# Bike_Alpha.net
KiCad netlist of a schematic drawn in EasyEDA
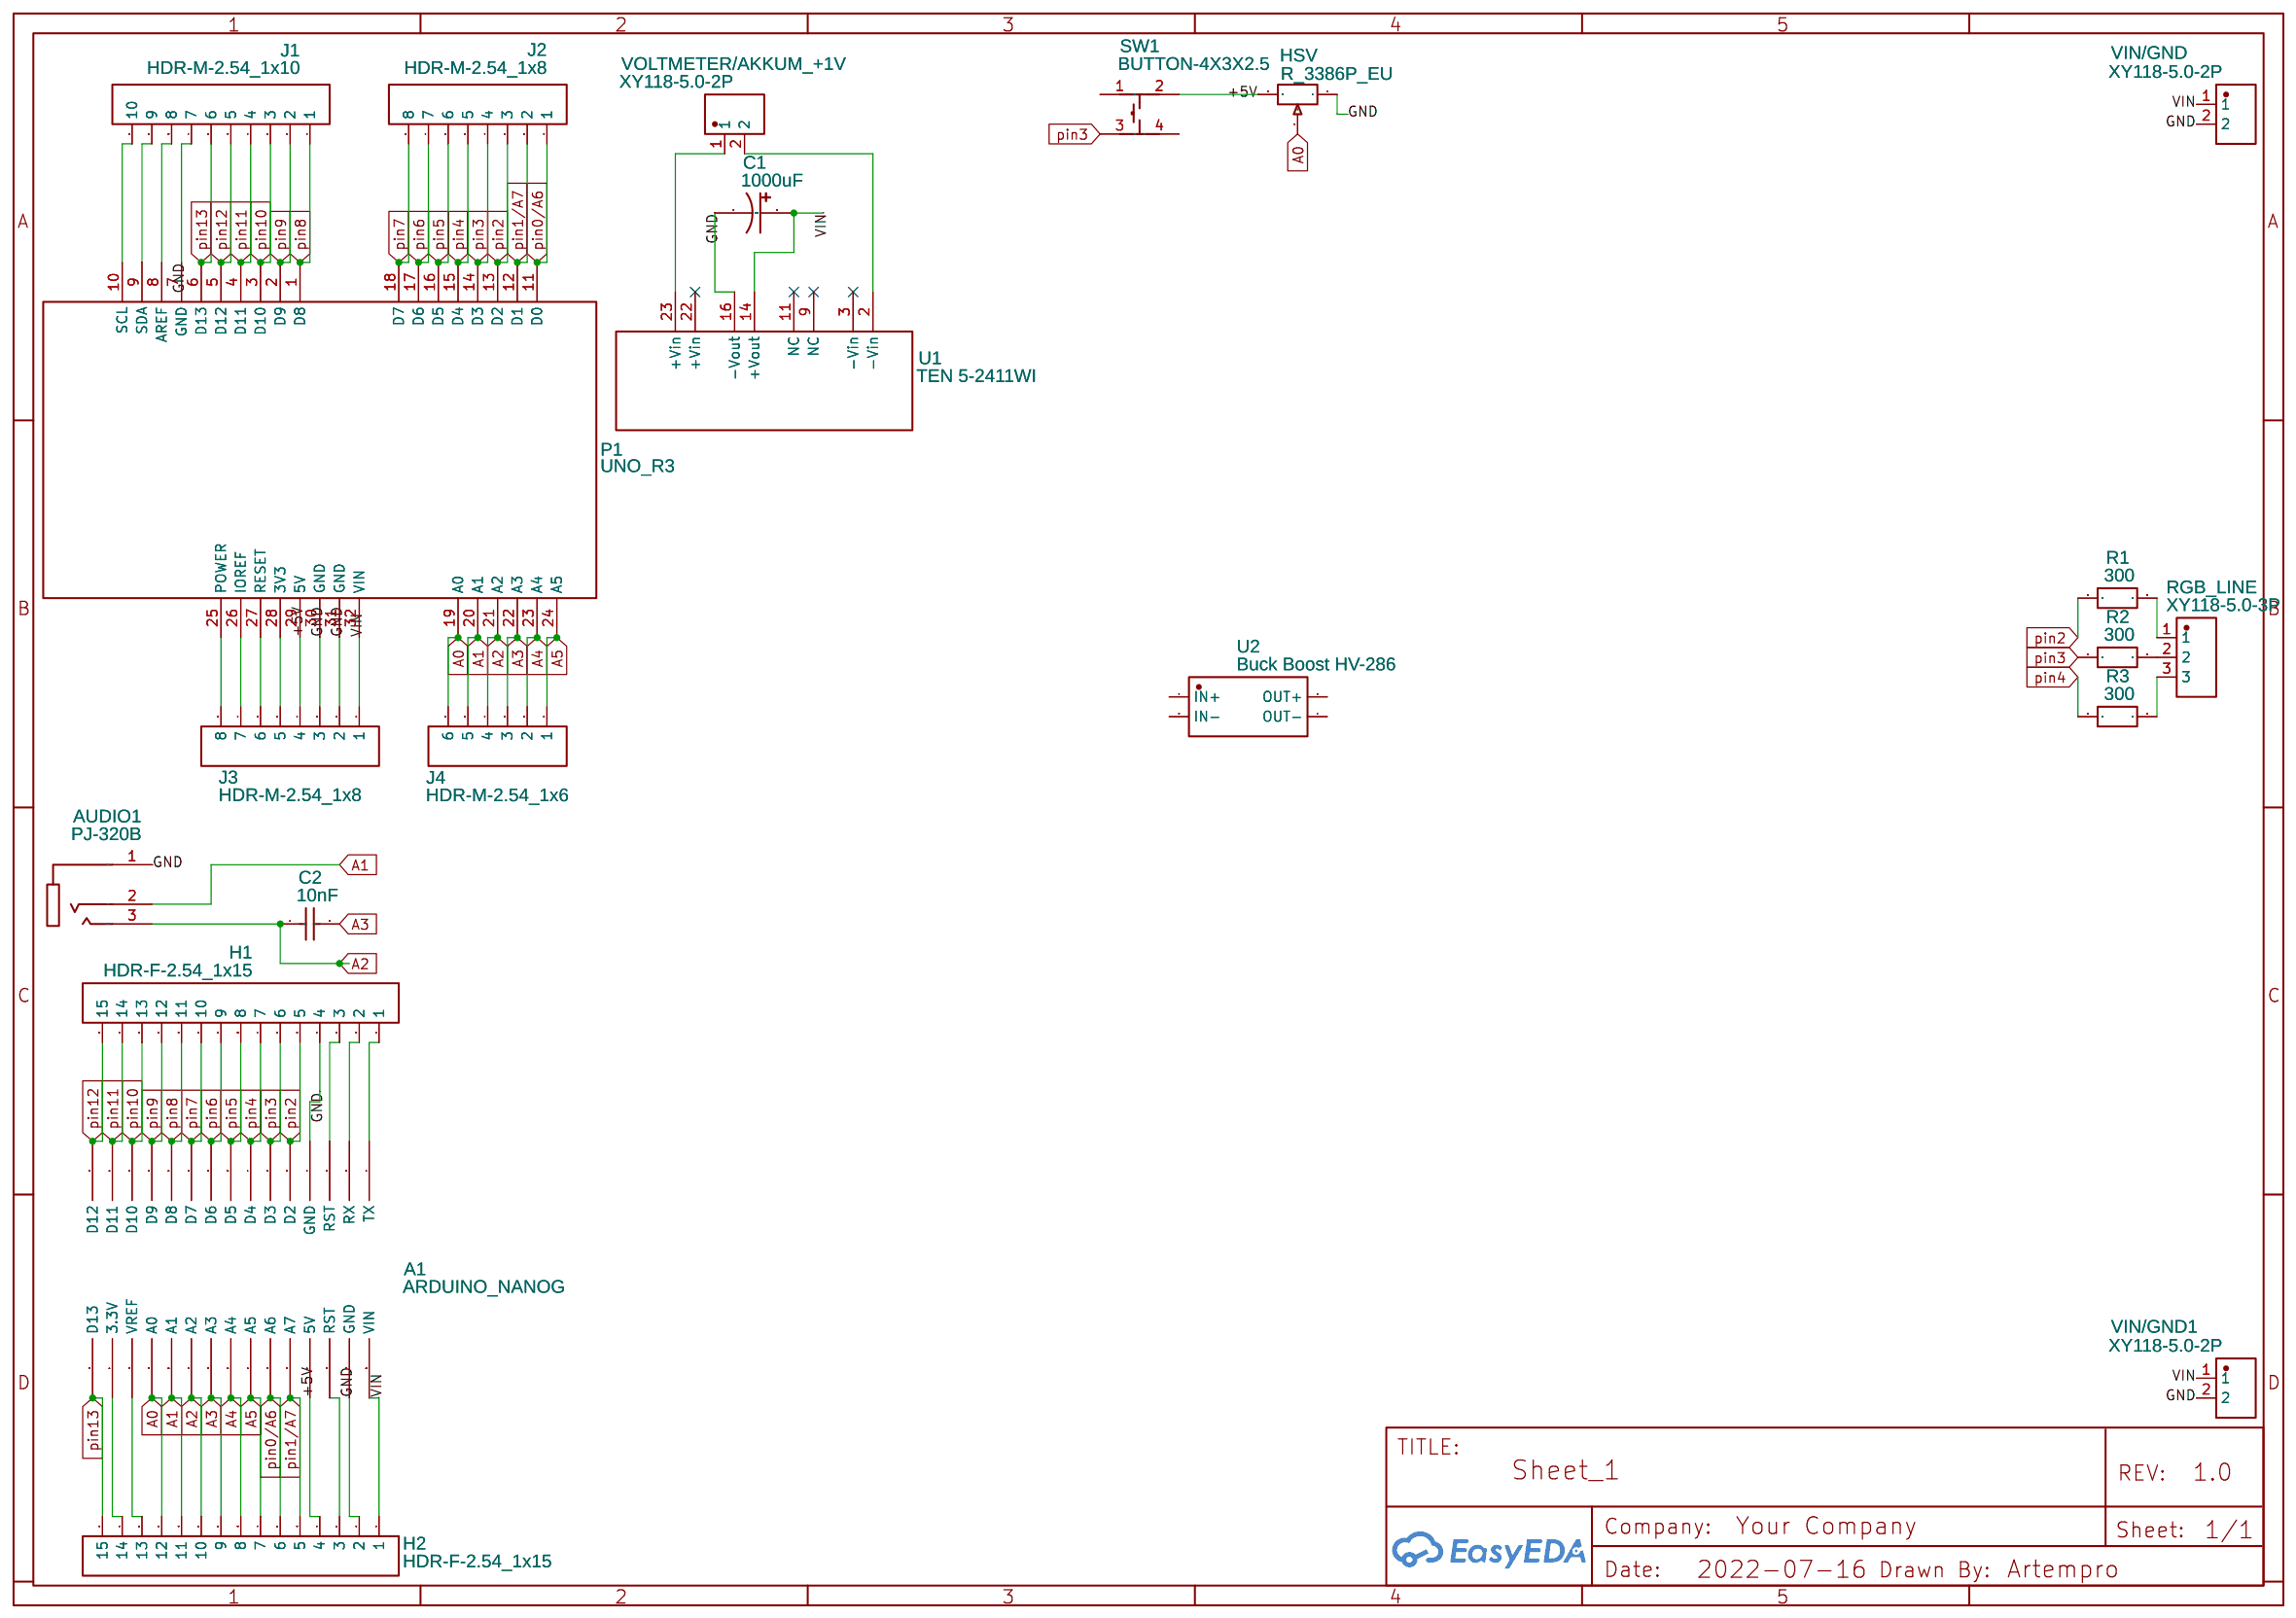
[diagram p0: Sheet_1]
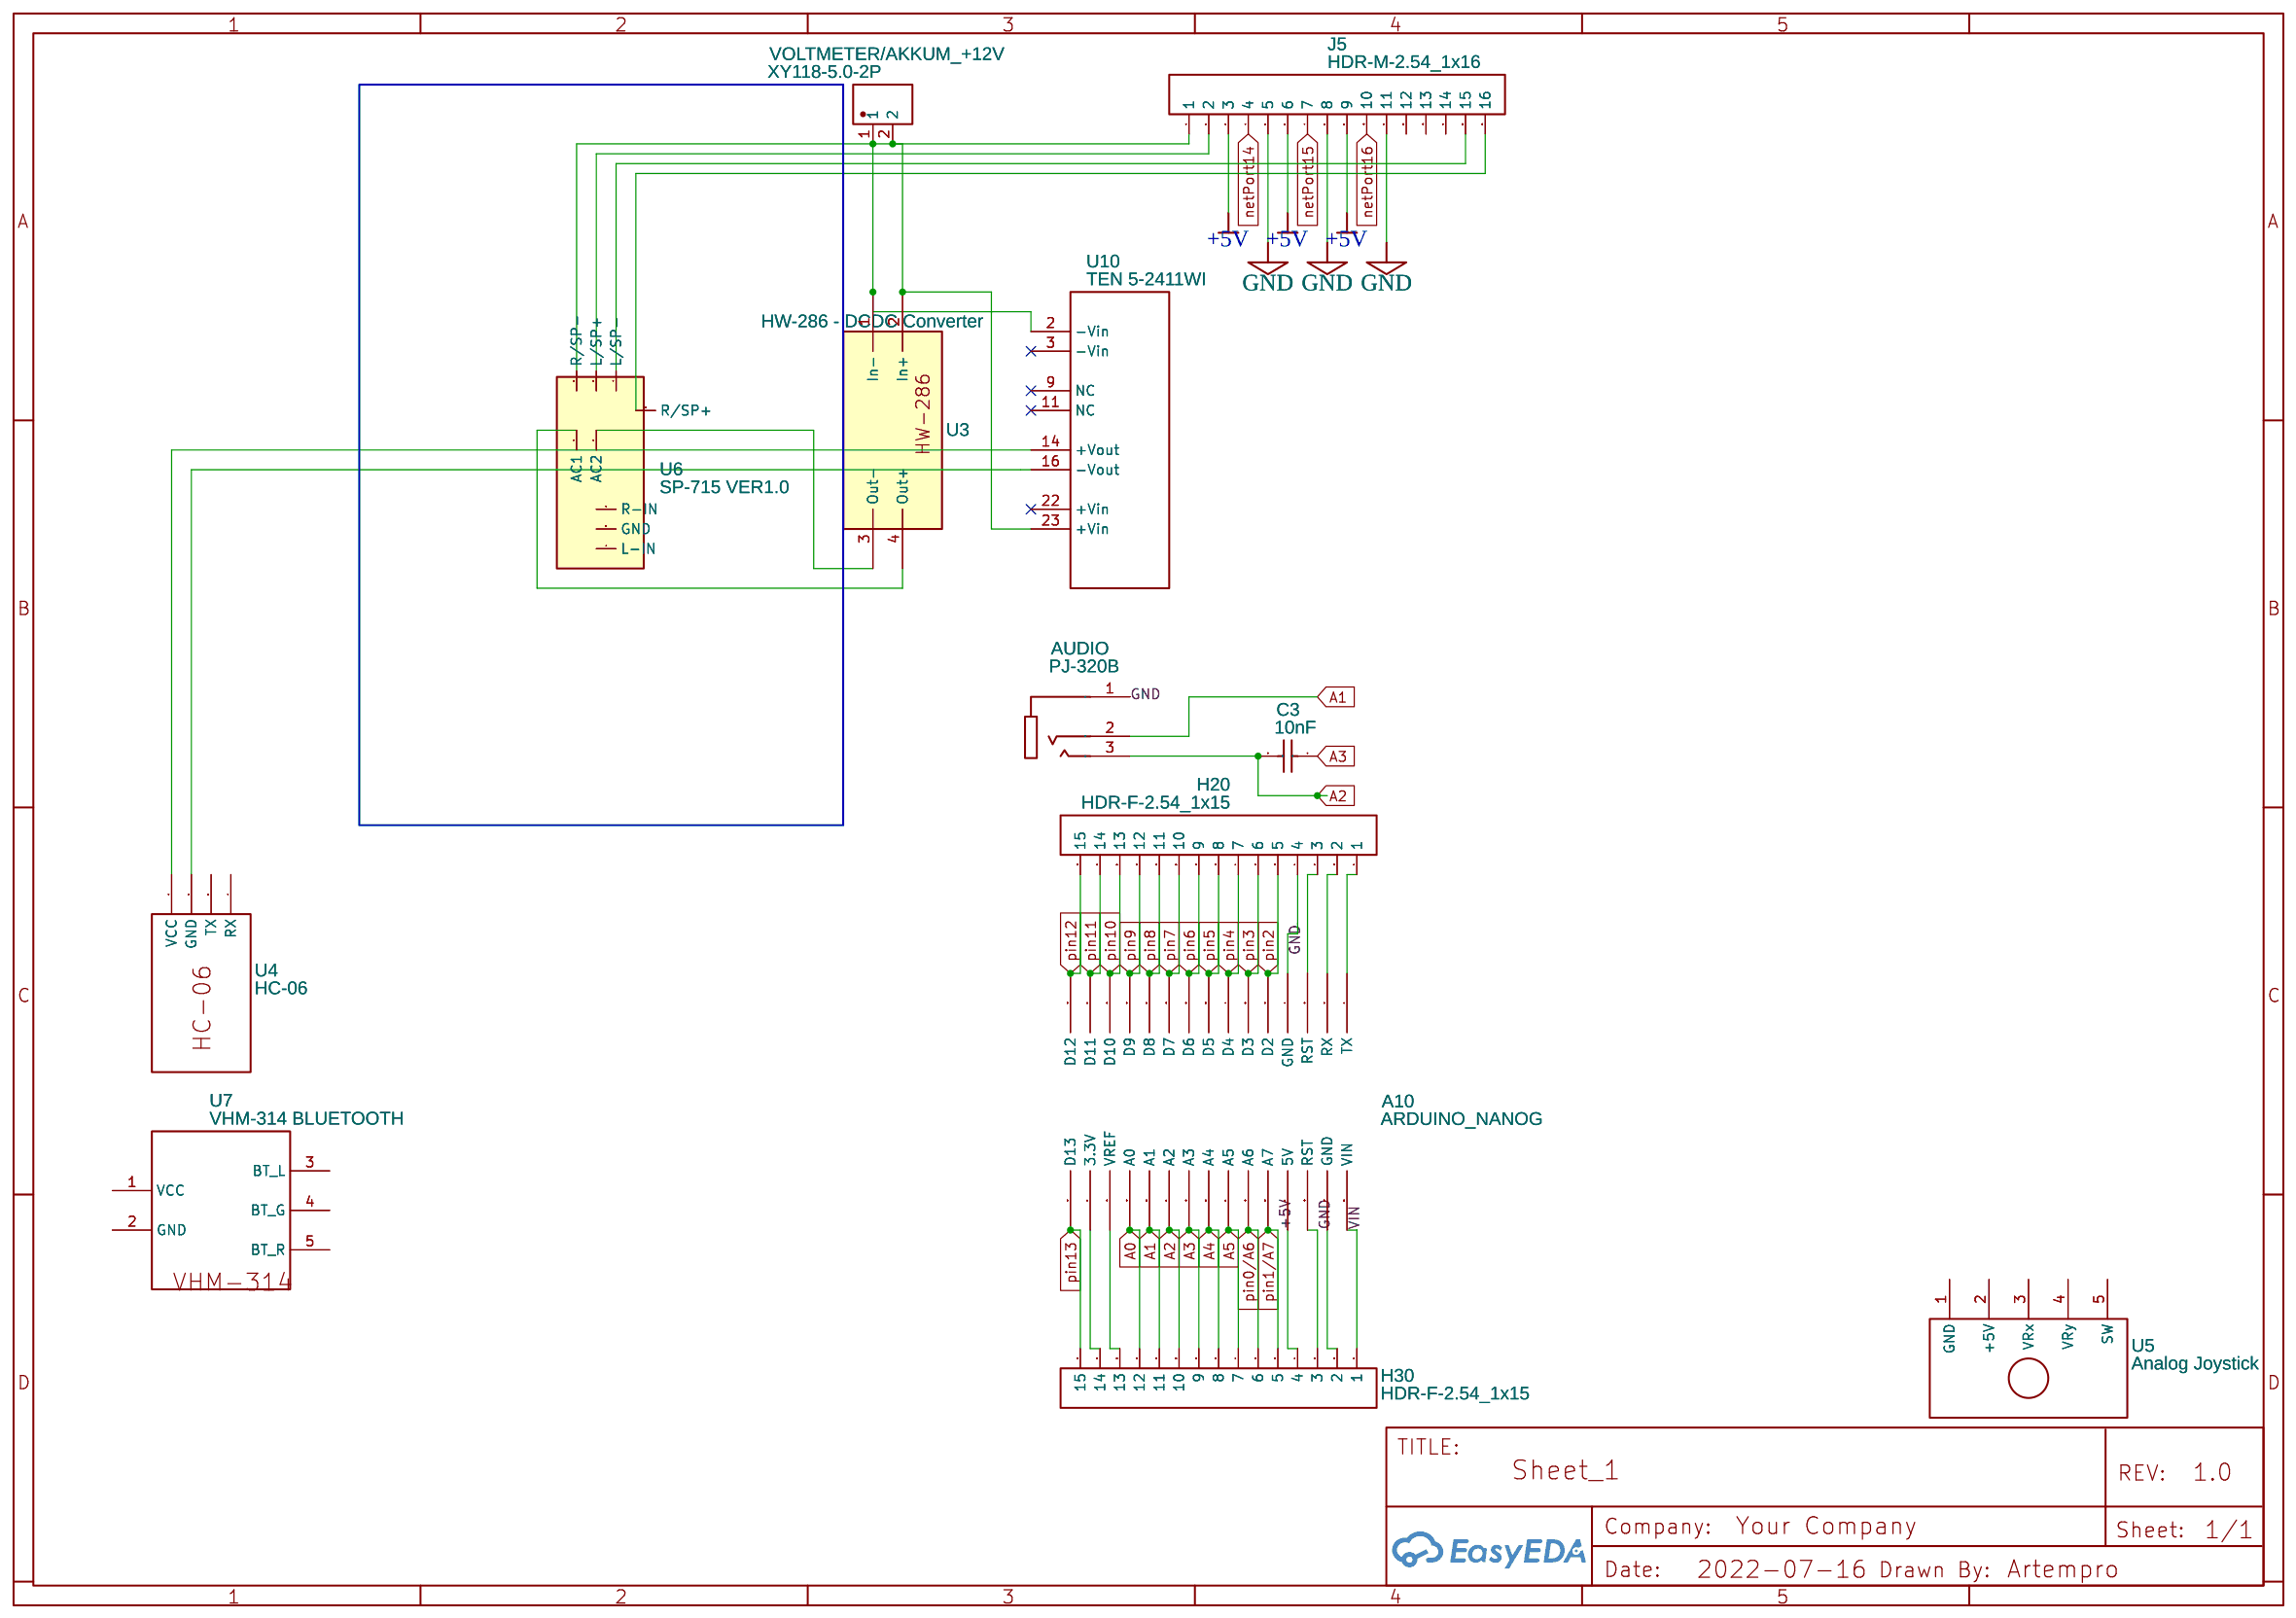
[diagram p1: Add multi media]

(export (version "E")
  (design (tool "Eeschema 10.0.6"))
  (components
    (comp (ref "A1")
      (value "ARDUINO_NANOG")
      (fields (field (name "BOM_Manufacturer Part") "Arduino Nano"))
      (libsource (lib "") (part "ARDUINO_NANOG"))
    )
    (comp (ref "AUDIO1")
      (value "PJ-320B")
      (fields (field (name "BOM_Supplier Part") "C18594"))
      (libsource (lib "") (part "PJ-320B"))
    )
    (comp (ref "C1")
      (value "1000uF")
      (fields
        (field (name "BOM_Manufacturer Part") "RGA102MOJBK-0811")
        (field (name "BOM_Supplier Part") "C311644")
      )
      (libsource (lib "") (part "RGA102MOJBK-0811"))
    )
    (comp (ref "C2")
      (value "10nF")
      (fields
        (field (name "BOM_Manufacturer Part") "DE2F3KY103MN3AM02F")
        (field (name "BOM_Supplier Part") "C85855")
      )
      (libsource (lib "") (part "DE2F3KY103MN3AM02F"))
    )
    (comp (ref "H1")
      (value "HDR-F-2.54_1x15")
      (fields (field (name "BOM_Supplier Part") "C124408"))
      (libsource (lib "") (part "HDR-F-2.54_1x15"))
    )
    (comp (ref "H2")
      (value "HDR-F-2.54_1x15")
      (fields (field (name "BOM_Supplier Part") "C124408"))
      (libsource (lib "") (part "HDR-F-2.54_1x15_1"))
    )
    (comp (ref "HSV") (value "R_3386P_EU") (libsource (lib "") (part "R_3386P_EU")))
    (comp (ref "J1")
      (value "HDR-M-2.54_1x10")
      (fields (field (name "BOM_Supplier Part") "C57369"))
      (libsource (lib "") (part "HDR-M-2.54_1x10"))
    )
    (comp (ref "J2")
      (value "HDR-M-2.54_1x8")
      (fields (field (name "BOM_Supplier Part") "C190820"))
      (libsource (lib "") (part "HDR-M-2.54_1x8"))
    )
    (comp (ref "J3")
      (value "HDR-M-2.54_1x8")
      (fields (field (name "BOM_Supplier Part") "C190820"))
      (libsource (lib "") (part "HDR-M-2.54_1x8_1"))
    )
    (comp (ref "J4")
      (value "HDR-M-2.54_1x6")
      (fields (field (name "BOM_Supplier Part") "C190819"))
      (libsource (lib "") (part "HDR-M-2.54_1x6"))
    )
    (comp (ref "P1") (value "UNO_R3") (libsource (lib "") (part "UNO_R3")))
    (comp (ref "R1")
      (value "300")
      (fields
        (field (name "BOM_Manufacturer Part") "RD 1/4W 300R J T/B A1")
        (field (name "BOM_Supplier Part") "C433735")
      )
      (libsource (lib "") (part "RD 1/4W 300R J T/B A1"))
    )
    (comp (ref "R2")
      (value "300")
      (fields
        (field (name "BOM_Manufacturer Part") "RD 1/4W 300R J T/B A1")
        (field (name "BOM_Supplier Part") "C433735")
      )
      (libsource (lib "") (part "RD 1/4W 300R J T/B A1"))
    )
    (comp (ref "R3")
      (value "300")
      (fields
        (field (name "BOM_Manufacturer Part") "RD 1/4W 300R J T/B A1")
        (field (name "BOM_Supplier Part") "C433735")
      )
      (libsource (lib "") (part "RD 1/4W 300R J T/B A1"))
    )
    (comp (ref "RGB_LINE")
      (value "XY118-5.0-3P")
      (fields (field (name "BOM_Supplier Part") "C784923"))
      (libsource (lib "") (part "XY118-5.0-3P"))
    )
    (comp (ref "SW1")
      (value "BUTTON-4X3X2.5")
      (fields (field (name "BOM_Supplier Part") "C9900020294"))
      (libsource (lib "") (part "BUTTON-4X3X2.5"))
    )
    (comp (ref "U1") (value "TEN 5-2411WI") (libsource (lib "") (part "TEN 5-2411WI")))
    (comp (ref "U2") (value "Buck Boost HV-286") (libsource (lib "") (part "Buck Boost HV-286")))
    (comp (ref "VIN/GND")
      (value "XY118-5.0-2P")
      (fields (field (name "BOM_Supplier Part") "C784922"))
      (libsource (lib "") (part "XY118-5.0-2P"))
    )
    (comp (ref "VIN/GND1")
      (value "XY118-5.0-2P")
      (fields (field (name "BOM_Supplier Part") "C784922"))
      (libsource (lib "") (part "XY118-5.0-2P"))
    )
    (comp (ref "VOLTMETER/AKKUM_+1V")
      (value "XY118-5.0-2P")
      (fields (field (name "BOM_Supplier Part") "C784922"))
      (libsource (lib "") (part "XY118-5.0-2P_1"))
    )
    (comp (ref "A10")
      (value "ARDUINO_NANOG")
      (fields (field (name "BOM_Manufacturer Part") "Arduino Nano"))
      (libsource (lib "") (part "ARDUINO_NANOG"))
    )
    (comp (ref "AUDIO")
      (value "PJ-320B")
      (fields (field (name "BOM_Supplier Part") "C18594"))
      (libsource (lib "") (part "PJ-320B"))
    )
    (comp (ref "C3")
      (value "10nF")
      (fields
        (field (name "BOM_Manufacturer Part") "DE2F3KY103MN3AM02F")
        (field (name "BOM_Supplier Part") "C85855")
      )
      (libsource (lib "") (part "DE2F3KY103MN3AM02F"))
    )
    (comp (ref "H20")
      (value "HDR-F-2.54_1x15")
      (fields (field (name "BOM_Supplier Part") "C124408"))
      (libsource (lib "") (part "HDR-F-2.54_1x15"))
    )
    (comp (ref "H30")
      (value "HDR-F-2.54_1x15")
      (fields (field (name "BOM_Supplier Part") "C124408"))
      (libsource (lib "") (part "HDR-F-2.54_1x15_1"))
    )
    (comp (ref "J5") (value "HDR-M-2.54_1x16") (libsource (lib "") (part "HDR-M-2.54_1x16")))
    (comp (ref "U3")
      (value "HW-286 - DCDC Converter")
      (fields (field (name "BOM_Supplier Part") "HW-286"))
      (libsource (lib "") (part "HW-286 - DCDC Converter"))
    )
    (comp (ref "U4") (value "HC-06") (libsource (lib "") (part "HC-06")))
    (comp (ref "U5") (value "Analog Joystick") (libsource (lib "") (part "Analog Joystick")))
    (comp (ref "U6")
      (value "SP-715 VER1.0")
      (fields (field (name "BOM_Manufacturer Part") "SP-715 VER 1.0"))
      (libsource (lib "") (part "SP-715 VER1.0"))
    )
    (comp (ref "U7")
      (value "VHM-314 BLUETOOTH")
      (fields (field (name "BOM_Manufacturer Part") "VHM-314"))
      (libsource (lib "") (part "VHM-314 BLUETOOTH"))
    )
    (comp (ref "U10") (value "TEN 5-2411WI") (libsource (lib "") (part "TEN 5-2411WI")))
    (comp (ref "VOLTMETER/AKKUM_+12V")
      (value "XY118-5.0-2P")
      (fields (field (name "BOM_Supplier Part") "C784922"))
      (libsource (lib "") (part "XY118-5.0-2P"))
    )
  )
  (nets
    (net (code "1") (name "+5V") (class "Default")
      (node (ref "A1") (pin "27") (pinfunction "5V_27") (pintype "unspecified"))
      (node (ref "A10") (pin "27") (pinfunction "5V_27") (pintype "unspecified"))
      (node (ref "H2") (pin "4") (pinfunction "4_4") (pintype "unspecified"))
      (node (ref "H30") (pin "4") (pinfunction "4_4") (pintype "unspecified"))
      (node (ref "HSV") (pin "3") (pinfunction "3_3") (pintype "input"))
      (node (ref "J3") (pin "4") (pinfunction "4_4") (pintype "unspecified"))
      (node (ref "J5") (pin "3") (pinfunction "3_3") (pintype "unspecified"))
      (node (ref "J5") (pin "6") (pinfunction "6_6") (pintype "unspecified"))
      (node (ref "J5") (pin "9") (pinfunction "9_9") (pintype "unspecified"))
      (node (ref "P1") (pin "29") (pinfunction "5V_29") (pintype "unspecified"))
      (node (ref "SW1") (pin "2") (pinfunction "2_2") (pintype "unspecified"))
    )
    (net (code "2") (name "A0") (class "Default")
      (node (ref "A1") (pin "19") (pinfunction "A0_19") (pintype "unspecified"))
      (node (ref "A10") (pin "19") (pinfunction "A0_19") (pintype "unspecified"))
      (node (ref "H2") (pin "12") (pinfunction "12_12") (pintype "unspecified"))
      (node (ref "H30") (pin "12") (pinfunction "12_12") (pintype "unspecified"))
      (node (ref "HSV") (pin "2") (pinfunction "2_2") (pintype "input"))
      (node (ref "J4") (pin "6") (pinfunction "6_6") (pintype "input"))
      (node (ref "P1") (pin "19") (pinfunction "A0_19") (pintype "unspecified"))
    )
    (net (code "3") (name "A1") (class "Default")
      (node (ref "A1") (pin "20") (pinfunction "A1_20") (pintype "unspecified"))
      (node (ref "A10") (pin "20") (pinfunction "A1_20") (pintype "unspecified"))
      (node (ref "AUDIO") (pin "2") (pinfunction "2_2") (pintype "unspecified"))
      (node (ref "AUDIO1") (pin "2") (pinfunction "2_2") (pintype "unspecified"))
      (node (ref "H2") (pin "11") (pinfunction "11_11") (pintype "unspecified"))
      (node (ref "H30") (pin "11") (pinfunction "11_11") (pintype "unspecified"))
      (node (ref "J4") (pin "5") (pinfunction "5_5") (pintype "input"))
      (node (ref "P1") (pin "20") (pinfunction "A1_20") (pintype "unspecified"))
    )
    (net (code "4") (name "A2") (class "Default")
      (node (ref "A1") (pin "21") (pinfunction "A2_21") (pintype "unspecified"))
      (node (ref "A10") (pin "21") (pinfunction "A2_21") (pintype "unspecified"))
      (node (ref "AUDIO") (pin "3") (pinfunction "3_3") (pintype "unspecified"))
      (node (ref "AUDIO1") (pin "3") (pinfunction "3_3") (pintype "unspecified"))
      (node (ref "C2") (pin "2") (pinfunction "2_2") (pintype "input"))
      (node (ref "C3") (pin "2") (pinfunction "2_2") (pintype "input"))
      (node (ref "H2") (pin "10") (pinfunction "10_10") (pintype "unspecified"))
      (node (ref "H30") (pin "10") (pinfunction "10_10") (pintype "unspecified"))
      (node (ref "J4") (pin "4") (pinfunction "4_4") (pintype "input"))
      (node (ref "P1") (pin "21") (pinfunction "A2_21") (pintype "unspecified"))
    )
    (net (code "5") (name "A3") (class "Default")
      (node (ref "A1") (pin "22") (pinfunction "A3_22") (pintype "unspecified"))
      (node (ref "A10") (pin "22") (pinfunction "A3_22") (pintype "unspecified"))
      (node (ref "C2") (pin "1") (pinfunction "1_1") (pintype "input"))
      (node (ref "C3") (pin "1") (pinfunction "1_1") (pintype "input"))
      (node (ref "H2") (pin "9") (pinfunction "9_9") (pintype "unspecified"))
      (node (ref "H30") (pin "9") (pinfunction "9_9") (pintype "unspecified"))
      (node (ref "J4") (pin "3") (pinfunction "3_3") (pintype "input"))
      (node (ref "P1") (pin "22") (pinfunction "A3_22") (pintype "unspecified"))
    )
    (net (code "6") (name "A4") (class "Default")
      (node (ref "A1") (pin "23") (pinfunction "A4_23") (pintype "unspecified"))
      (node (ref "A10") (pin "23") (pinfunction "A4_23") (pintype "unspecified"))
      (node (ref "H2") (pin "8") (pinfunction "8_8") (pintype "unspecified"))
      (node (ref "H30") (pin "8") (pinfunction "8_8") (pintype "unspecified"))
      (node (ref "J4") (pin "2") (pinfunction "2_2") (pintype "input"))
      (node (ref "P1") (pin "23") (pinfunction "A4_23") (pintype "unspecified"))
    )
    (net (code "7") (name "A5") (class "Default")
      (node (ref "A1") (pin "24") (pinfunction "A5_24") (pintype "unspecified"))
      (node (ref "A10") (pin "24") (pinfunction "A5_24") (pintype "unspecified"))
      (node (ref "H2") (pin "7") (pinfunction "7_7") (pintype "unspecified"))
      (node (ref "H30") (pin "7") (pinfunction "7_7") (pintype "unspecified"))
      (node (ref "J4") (pin "1") (pinfunction "1_1") (pintype "input"))
      (node (ref "P1") (pin "24") (pinfunction "A5_24") (pintype "unspecified"))
    )
    (net (code "8") (name "GND") (class "Default")
      (node (ref "A1") (pin "29") (pinfunction "GND_29") (pintype "unspecified"))
      (node (ref "A1") (pin "4") (pinfunction "GND_4") (pintype "unspecified"))
      (node (ref "A10") (pin "29") (pinfunction "GND_29") (pintype "unspecified"))
      (node (ref "A10") (pin "4") (pinfunction "GND_4") (pintype "unspecified"))
      (node (ref "AUDIO") (pin "1") (pinfunction "1_1") (pintype "unspecified"))
      (node (ref "AUDIO1") (pin "1") (pinfunction "1_1") (pintype "unspecified"))
      (node (ref "C1") (pin "2") (pinfunction "2_2") (pintype "unspecified"))
      (node (ref "H1") (pin "4") (pinfunction "4_4") (pintype "unspecified"))
      (node (ref "H2") (pin "2") (pinfunction "2_2") (pintype "unspecified"))
      (node (ref "H20") (pin "4") (pinfunction "4_4") (pintype "unspecified"))
      (node (ref "H30") (pin "2") (pinfunction "2_2") (pintype "unspecified"))
      (node (ref "HSV") (pin "1") (pinfunction "1_1") (pintype "input"))
      (node (ref "J1") (pin "7") (pinfunction "7_7") (pintype "unspecified"))
      (node (ref "J3") (pin "2") (pinfunction "2_2") (pintype "unspecified"))
      (node (ref "J3") (pin "3") (pinfunction "3_3") (pintype "unspecified"))
      (node (ref "J5") (pin "11") (pinfunction "11_11") (pintype "unspecified"))
      (node (ref "J5") (pin "5") (pinfunction "5_5") (pintype "unspecified"))
      (node (ref "J5") (pin "8") (pinfunction "8_8") (pintype "unspecified"))
      (node (ref "P1") (pin "30") (pinfunction "GND_30") (pintype "unspecified"))
      (node (ref "P1") (pin "31") (pinfunction "GND_31") (pintype "unspecified"))
      (node (ref "P1") (pin "7") (pinfunction "GND_7") (pintype "unspecified"))
      (node (ref "U1") (pin "16") (pinfunction "-Vout_16") (pintype "unspecified"))
      (node (ref "VIN/GND") (pin "2") (pinfunction "2_2") (pintype "unspecified"))
      (node (ref "VIN/GND1") (pin "2") (pinfunction "2_2") (pintype "unspecified"))
    )
    (net (code "9") (name "Net-(A1-3.3V)") (class "Default")
      (node (ref "A1") (pin "17") (pinfunction "3.3V_17") (pintype "unspecified"))
      (node (ref "H2") (pin "14") (pinfunction "14_14") (pintype "unspecified"))
    )
    (net (code "10") (name "Net-(A1-RST-Pad3)") (class "Default")
      (node (ref "A1") (pin "3") (pinfunction "RST_3") (pintype "unspecified"))
      (node (ref "H1") (pin "3") (pinfunction "3_3") (pintype "unspecified"))
    )
    (net (code "11") (name "Net-(A1-RST-Pad28)") (class "Default")
      (node (ref "A1") (pin "28") (pinfunction "RST_28") (pintype "unspecified"))
      (node (ref "H2") (pin "3") (pinfunction "3_3") (pintype "unspecified"))
    )
    (net (code "12") (name "Net-(A1-RX)") (class "Default")
      (node (ref "A1") (pin "2") (pinfunction "RX_2") (pintype "unspecified"))
      (node (ref "H1") (pin "2") (pinfunction "2_2") (pintype "unspecified"))
    )
    (net (code "13") (name "Net-(A1-TX)") (class "Default")
      (node (ref "A1") (pin "1") (pinfunction "TX_1") (pintype "unspecified"))
      (node (ref "H1") (pin "1") (pinfunction "1_1") (pintype "unspecified"))
    )
    (net (code "14") (name "Net-(A1-VREF)") (class "Default")
      (node (ref "A1") (pin "18") (pinfunction "VREF_18") (pintype "unspecified"))
      (node (ref "H2") (pin "13") (pinfunction "13_13") (pintype "unspecified"))
    )
    (net (code "15") (name "Net-(A10-3.3V)") (class "Default")
      (node (ref "A10") (pin "17") (pinfunction "3.3V_17") (pintype "unspecified"))
      (node (ref "H30") (pin "14") (pinfunction "14_14") (pintype "unspecified"))
    )
    (net (code "16") (name "Net-(A10-RST-Pad3)") (class "Default")
      (node (ref "A10") (pin "3") (pinfunction "RST_3") (pintype "unspecified"))
      (node (ref "H20") (pin "3") (pinfunction "3_3") (pintype "unspecified"))
    )
    (net (code "17") (name "Net-(A10-RST-Pad28)") (class "Default")
      (node (ref "A10") (pin "28") (pinfunction "RST_28") (pintype "unspecified"))
      (node (ref "H30") (pin "3") (pinfunction "3_3") (pintype "unspecified"))
    )
    (net (code "18") (name "Net-(A10-RX)") (class "Default")
      (node (ref "A10") (pin "2") (pinfunction "RX_2") (pintype "unspecified"))
      (node (ref "H20") (pin "2") (pinfunction "2_2") (pintype "unspecified"))
    )
    (net (code "19") (name "Net-(A10-TX)") (class "Default")
      (node (ref "A10") (pin "1") (pinfunction "TX_1") (pintype "unspecified"))
      (node (ref "H20") (pin "1") (pinfunction "1_1") (pintype "unspecified"))
    )
    (net (code "20") (name "Net-(A10-VREF)") (class "Default")
      (node (ref "A10") (pin "18") (pinfunction "VREF_18") (pintype "unspecified"))
      (node (ref "H30") (pin "13") (pinfunction "13_13") (pintype "unspecified"))
    )
    (net (code "21") (name "Net-(P1-3V3)") (class "Default")
      (node (ref "J3") (pin "5") (pinfunction "5_5") (pintype "unspecified"))
      (node (ref "P1") (pin "28") (pinfunction "3V3_28") (pintype "unspecified"))
    )
    (net (code "22") (name "Net-(P1-AREF)") (class "Default")
      (node (ref "J1") (pin "8") (pinfunction "8_8") (pintype "unspecified"))
      (node (ref "P1") (pin "8") (pinfunction "AREF_8") (pintype "unspecified"))
    )
    (net (code "23") (name "Net-(P1-IOREF)") (class "Default")
      (node (ref "J3") (pin "7") (pinfunction "7_7") (pintype "unspecified"))
      (node (ref "P1") (pin "26") (pinfunction "IOREF_26") (pintype "unspecified"))
    )
    (net (code "24") (name "Net-(P1-POWER)") (class "Default")
      (node (ref "J3") (pin "8") (pinfunction "8_8") (pintype "unspecified"))
      (node (ref "P1") (pin "25") (pinfunction "POWER_25") (pintype "unspecified"))
    )
    (net (code "25") (name "Net-(P1-RESET)") (class "Default")
      (node (ref "J3") (pin "6") (pinfunction "6_6") (pintype "unspecified"))
      (node (ref "P1") (pin "27") (pinfunction "RESET_27") (pintype "unspecified"))
    )
    (net (code "26") (name "Net-(P1-SCL)") (class "Default")
      (node (ref "J1") (pin "10") (pinfunction "10_10") (pintype "unspecified"))
      (node (ref "P1") (pin "10") (pinfunction "SCL_10") (pintype "unspecified"))
    )
    (net (code "27") (name "Net-(P1-SDA)") (class "Default")
      (node (ref "J1") (pin "9") (pinfunction "9_9") (pintype "unspecified"))
      (node (ref "P1") (pin "9") (pinfunction "SDA_9") (pintype "unspecified"))
    )
    (net (code "28") (name "Net-(R1-Pad2)") (class "Default")
      (node (ref "R1") (pin "2") (pinfunction "2_2") (pintype "unspecified"))
      (node (ref "RGB_LINE") (pin "1") (pinfunction "1_1") (pintype "unspecified"))
    )
    (net (code "29") (name "Net-(R2-Pad2)") (class "Default")
      (node (ref "R2") (pin "2") (pinfunction "2_2") (pintype "unspecified"))
      (node (ref "RGB_LINE") (pin "2") (pinfunction "2_2") (pintype "unspecified"))
    )
    (net (code "30") (name "Net-(R3-Pad2)") (class "Default")
      (node (ref "R3") (pin "2") (pinfunction "2_2") (pintype "unspecified"))
      (node (ref "RGB_LINE") (pin "3") (pinfunction "3_3") (pintype "unspecified"))
    )
    (net (code "31") (name "Net-(U1-+Vin-Pad23)") (class "Default")
      (node (ref "U1") (pin "23") (pinfunction "+Vin_23") (pintype "unspecified"))
      (node (ref "VOLTMETER/AKKUM_+1V") (pin "1") (pinfunction "1_1") (pintype "unspecified"))
    )
    (net (code "32") (name "Net-(U1--Vin-Pad2)") (class "Default")
      (node (ref "U1") (pin "2") (pinfunction "-Vin_2") (pintype "unspecified"))
      (node (ref "VOLTMETER/AKKUM_+1V") (pin "2") (pinfunction "2_2") (pintype "unspecified"))
    )
    (net (code "33") (name "Net-(U3-In+)") (class "Default")
      (node (ref "J5") (pin "1") (pinfunction "1_1") (pintype "unspecified"))
      (node (ref "U10") (pin "2") (pinfunction "-Vin_2") (pintype "unspecified"))
      (node (ref "U10") (pin "23") (pinfunction "+Vin_23") (pintype "unspecified"))
      (node (ref "U3") (pin "1") (pinfunction "In-_1") (pintype "unspecified"))
      (node (ref "U3") (pin "2") (pinfunction "In+_2") (pintype "unspecified"))
      (node (ref "U6") (pin "3") (pinfunction "R/SP-_3") (pintype "unspecified"))
      (node (ref "VOLTMETER/AKKUM_+12V") (pin "1") (pinfunction "1_1") (pintype "unspecified"))
      (node (ref "VOLTMETER/AKKUM_+12V") (pin "2") (pinfunction "2_2") (pintype "unspecified"))
    )
    (net (code "34") (name "Net-(U3-Out+)") (class "Default")
      (node (ref "U3") (pin "4") (pinfunction "Out+_4") (pintype "unspecified"))
      (node (ref "U6") (pin "1") (pinfunction "AC1_1") (pintype "unspecified"))
    )
    (net (code "35") (name "Net-(U3-Out-)") (class "Default")
      (node (ref "U3") (pin "3") (pinfunction "Out-_3") (pintype "unspecified"))
      (node (ref "U6") (pin "2") (pinfunction "AC2_2") (pintype "unspecified"))
    )
    (net (code "36") (name "Net-(U6-L{slash}SP+)") (class "Default")
      (node (ref "J5") (pin "2") (pinfunction "2_2") (pintype "unspecified"))
      (node (ref "U6") (pin "5") (pinfunction "L/SP+_5") (pintype "unspecified"))
    )
    (net (code "37") (name "Net-(U6-L{slash}SP-)") (class "Default")
      (node (ref "J5") (pin "15") (pinfunction "15_15") (pintype "unspecified"))
      (node (ref "U6") (pin "4") (pinfunction "L/SP-_4") (pintype "unspecified"))
    )
    (net (code "38") (name "Net-(U6-R{slash}SP+)") (class "Default")
      (node (ref "J5") (pin "16") (pinfunction "16_16") (pintype "unspecified"))
      (node (ref "U6") (pin "6") (pinfunction "R/SP+_6") (pintype "unspecified"))
    )
    (net (code "39") (name "Net-(U10-+Vout)") (class "Default")
      (node (ref "U10") (pin "14") (pinfunction "+Vout_14") (pintype "unspecified"))
      (node (ref "U4") (pin "1") (pinfunction "VCC_1") (pintype "unspecified"))
    )
    (net (code "40") (name "Net-(U10--Vout)") (class "Default")
      (node (ref "U10") (pin "16") (pinfunction "-Vout_16") (pintype "unspecified"))
      (node (ref "U4") (pin "2") (pinfunction "GND_2") (pintype "unspecified"))
    )
    (net (code "41") (name "VIN") (class "Default")
      (node (ref "A1") (pin "30") (pinfunction "VIN_30") (pintype "unspecified"))
      (node (ref "A10") (pin "30") (pinfunction "VIN_30") (pintype "unspecified"))
      (node (ref "C1") (pin "1") (pinfunction "1_1") (pintype "unspecified"))
      (node (ref "H2") (pin "1") (pinfunction "1_1") (pintype "unspecified"))
      (node (ref "H30") (pin "1") (pinfunction "1_1") (pintype "unspecified"))
      (node (ref "J3") (pin "1") (pinfunction "1_1") (pintype "unspecified"))
      (node (ref "P1") (pin "32") (pinfunction "VIN_32") (pintype "unspecified"))
      (node (ref "U1") (pin "14") (pinfunction "+Vout_14") (pintype "unspecified"))
      (node (ref "VIN/GND") (pin "1") (pinfunction "1_1") (pintype "unspecified"))
      (node (ref "VIN/GND1") (pin "1") (pinfunction "1_1") (pintype "unspecified"))
    )
    (net (code "42") (name "netPort14") (class "Default")
      (node (ref "J5") (pin "4") (pinfunction "4_4") (pintype "unspecified"))
    )
    (net (code "43") (name "netPort15") (class "Default")
      (node (ref "J5") (pin "7") (pinfunction "7_7") (pintype "unspecified"))
    )
    (net (code "44") (name "netPort16") (class "Default")
      (node (ref "J5") (pin "10") (pinfunction "10_10") (pintype "unspecified"))
    )
    (net (code "45") (name "pin0{slash}A6") (class "Default")
      (node (ref "A1") (pin "25") (pinfunction "A6_25") (pintype "unspecified"))
      (node (ref "A10") (pin "25") (pinfunction "A6_25") (pintype "unspecified"))
      (node (ref "H2") (pin "6") (pinfunction "6_6") (pintype "unspecified"))
      (node (ref "H30") (pin "6") (pinfunction "6_6") (pintype "unspecified"))
      (node (ref "J2") (pin "1") (pinfunction "1_1") (pintype "unspecified"))
      (node (ref "P1") (pin "11") (pinfunction "D0_11") (pintype "unspecified"))
    )
    (net (code "46") (name "pin1{slash}A7") (class "Default")
      (node (ref "A1") (pin "26") (pinfunction "A7_26") (pintype "unspecified"))
      (node (ref "A10") (pin "26") (pinfunction "A7_26") (pintype "unspecified"))
      (node (ref "H2") (pin "5") (pinfunction "5_5") (pintype "unspecified"))
      (node (ref "H30") (pin "5") (pinfunction "5_5") (pintype "unspecified"))
      (node (ref "J2") (pin "2") (pinfunction "2_2") (pintype "unspecified"))
      (node (ref "P1") (pin "12") (pinfunction "D1_12") (pintype "unspecified"))
    )
    (net (code "47") (name "pin2") (class "Default")
      (node (ref "A1") (pin "5") (pinfunction "D2_5") (pintype "unspecified"))
      (node (ref "A10") (pin "5") (pinfunction "D2_5") (pintype "unspecified"))
      (node (ref "H1") (pin "5") (pinfunction "5_5") (pintype "unspecified"))
      (node (ref "H20") (pin "5") (pinfunction "5_5") (pintype "unspecified"))
      (node (ref "J2") (pin "3") (pinfunction "3_3") (pintype "unspecified"))
      (node (ref "P1") (pin "13") (pinfunction "D2_13") (pintype "unspecified"))
      (node (ref "R1") (pin "1") (pinfunction "1_1") (pintype "unspecified"))
    )
    (net (code "48") (name "pin3") (class "Default")
      (node (ref "A1") (pin "6") (pinfunction "D3_6") (pintype "unspecified"))
      (node (ref "A10") (pin "6") (pinfunction "D3_6") (pintype "unspecified"))
      (node (ref "H1") (pin "6") (pinfunction "6_6") (pintype "unspecified"))
      (node (ref "H20") (pin "6") (pinfunction "6_6") (pintype "unspecified"))
      (node (ref "J2") (pin "4") (pinfunction "4_4") (pintype "unspecified"))
      (node (ref "P1") (pin "14") (pinfunction "D3_14") (pintype "unspecified"))
      (node (ref "R2") (pin "1") (pinfunction "1_1") (pintype "unspecified"))
      (node (ref "SW1") (pin "3") (pinfunction "3_3") (pintype "unspecified"))
    )
    (net (code "49") (name "pin4") (class "Default")
      (node (ref "A1") (pin "7") (pinfunction "D4_7") (pintype "unspecified"))
      (node (ref "A10") (pin "7") (pinfunction "D4_7") (pintype "unspecified"))
      (node (ref "H1") (pin "7") (pinfunction "7_7") (pintype "unspecified"))
      (node (ref "H20") (pin "7") (pinfunction "7_7") (pintype "unspecified"))
      (node (ref "J2") (pin "5") (pinfunction "5_5") (pintype "unspecified"))
      (node (ref "P1") (pin "15") (pinfunction "D4_15") (pintype "unspecified"))
      (node (ref "R3") (pin "1") (pinfunction "1_1") (pintype "unspecified"))
    )
    (net (code "50") (name "pin5") (class "Default")
      (node (ref "A1") (pin "8") (pinfunction "D5_8") (pintype "unspecified"))
      (node (ref "A10") (pin "8") (pinfunction "D5_8") (pintype "unspecified"))
      (node (ref "H1") (pin "8") (pinfunction "8_8") (pintype "unspecified"))
      (node (ref "H20") (pin "8") (pinfunction "8_8") (pintype "unspecified"))
      (node (ref "J2") (pin "6") (pinfunction "6_6") (pintype "unspecified"))
      (node (ref "P1") (pin "16") (pinfunction "D5_16") (pintype "unspecified"))
    )
    (net (code "51") (name "pin6") (class "Default")
      (node (ref "A1") (pin "9") (pinfunction "D6_9") (pintype "unspecified"))
      (node (ref "A10") (pin "9") (pinfunction "D6_9") (pintype "unspecified"))
      (node (ref "H1") (pin "9") (pinfunction "9_9") (pintype "unspecified"))
      (node (ref "H20") (pin "9") (pinfunction "9_9") (pintype "unspecified"))
      (node (ref "J2") (pin "7") (pinfunction "7_7") (pintype "unspecified"))
      (node (ref "P1") (pin "17") (pinfunction "D6_17") (pintype "unspecified"))
    )
    (net (code "52") (name "pin7") (class "Default")
      (node (ref "A1") (pin "10") (pinfunction "D7_10") (pintype "unspecified"))
      (node (ref "A10") (pin "10") (pinfunction "D7_10") (pintype "unspecified"))
      (node (ref "H1") (pin "10") (pinfunction "10_10") (pintype "unspecified"))
      (node (ref "H20") (pin "10") (pinfunction "10_10") (pintype "unspecified"))
      (node (ref "J2") (pin "8") (pinfunction "8_8") (pintype "unspecified"))
      (node (ref "P1") (pin "18") (pinfunction "D7_18") (pintype "unspecified"))
    )
    (net (code "53") (name "pin8") (class "Default")
      (node (ref "A1") (pin "11") (pinfunction "D8_11") (pintype "unspecified"))
      (node (ref "A10") (pin "11") (pinfunction "D8_11") (pintype "unspecified"))
      (node (ref "H1") (pin "11") (pinfunction "11_11") (pintype "unspecified"))
      (node (ref "H20") (pin "11") (pinfunction "11_11") (pintype "unspecified"))
      (node (ref "J1") (pin "1") (pinfunction "1_1") (pintype "unspecified"))
      (node (ref "P1") (pin "1") (pinfunction "D8_1") (pintype "unspecified"))
    )
    (net (code "54") (name "pin9") (class "Default")
      (node (ref "A1") (pin "12") (pinfunction "D9_12") (pintype "unspecified"))
      (node (ref "A10") (pin "12") (pinfunction "D9_12") (pintype "unspecified"))
      (node (ref "H1") (pin "12") (pinfunction "12_12") (pintype "unspecified"))
      (node (ref "H20") (pin "12") (pinfunction "12_12") (pintype "unspecified"))
      (node (ref "J1") (pin "2") (pinfunction "2_2") (pintype "unspecified"))
      (node (ref "P1") (pin "2") (pinfunction "D9_2") (pintype "unspecified"))
    )
    (net (code "55") (name "pin10") (class "Default")
      (node (ref "A1") (pin "13") (pinfunction "D10_13") (pintype "unspecified"))
      (node (ref "A10") (pin "13") (pinfunction "D10_13") (pintype "unspecified"))
      (node (ref "H1") (pin "13") (pinfunction "13_13") (pintype "unspecified"))
      (node (ref "H20") (pin "13") (pinfunction "13_13") (pintype "unspecified"))
      (node (ref "J1") (pin "3") (pinfunction "3_3") (pintype "unspecified"))
      (node (ref "P1") (pin "3") (pinfunction "D10_3") (pintype "unspecified"))
    )
    (net (code "56") (name "pin11") (class "Default")
      (node (ref "A1") (pin "14") (pinfunction "D11_14") (pintype "unspecified"))
      (node (ref "A10") (pin "14") (pinfunction "D11_14") (pintype "unspecified"))
      (node (ref "H1") (pin "14") (pinfunction "14_14") (pintype "unspecified"))
      (node (ref "H20") (pin "14") (pinfunction "14_14") (pintype "unspecified"))
      (node (ref "J1") (pin "4") (pinfunction "4_4") (pintype "unspecified"))
      (node (ref "P1") (pin "4") (pinfunction "D11_4") (pintype "unspecified"))
    )
    (net (code "57") (name "pin12") (class "Default")
      (node (ref "A1") (pin "15") (pinfunction "D12_15") (pintype "unspecified"))
      (node (ref "A10") (pin "15") (pinfunction "D12_15") (pintype "unspecified"))
      (node (ref "H1") (pin "15") (pinfunction "15_15") (pintype "unspecified"))
      (node (ref "H20") (pin "15") (pinfunction "15_15") (pintype "unspecified"))
      (node (ref "J1") (pin "5") (pinfunction "5_5") (pintype "unspecified"))
      (node (ref "P1") (pin "5") (pinfunction "D12_5") (pintype "unspecified"))
    )
    (net (code "58") (name "pin13") (class "Default")
      (node (ref "A1") (pin "16") (pinfunction "D13_16") (pintype "unspecified"))
      (node (ref "A10") (pin "16") (pinfunction "D13_16") (pintype "unspecified"))
      (node (ref "H2") (pin "15") (pinfunction "15_15") (pintype "unspecified"))
      (node (ref "H30") (pin "15") (pinfunction "15_15") (pintype "unspecified"))
      (node (ref "J1") (pin "6") (pinfunction "6_6") (pintype "unspecified"))
      (node (ref "P1") (pin "6") (pinfunction "D13_6") (pintype "unspecified"))
    )
    (net (code "59") (name "unconnected-(J5-Pad12)") (class "Default")
      (node (ref "J5") (pin "12") (pinfunction "12_12") (pintype "unspecified"))
    )
    (net (code "60") (name "unconnected-(J5-Pad13)") (class "Default")
      (node (ref "J5") (pin "13") (pinfunction "13_13") (pintype "unspecified"))
    )
    (net (code "61") (name "unconnected-(J5-Pad14)") (class "Default")
      (node (ref "J5") (pin "14") (pinfunction "14_14") (pintype "unspecified"))
    )
    (net (code "62") (name "unconnected-(SW1-Pad1)") (class "Default")
      (node (ref "SW1") (pin "1") (pinfunction "1_1") (pintype "unspecified"))
    )
    (net (code "63") (name "unconnected-(SW1-Pad4)") (class "Default")
      (node (ref "SW1") (pin "4") (pinfunction "4_4") (pintype "unspecified"))
    )
    (net (code "64") (name "unconnected-(U1-+Vin-Pad22)") (class "Default")
      (node (ref "U1") (pin "22") (pinfunction "+Vin_22") (pintype "unspecified+no_connect"))
    )
    (net (code "65") (name "unconnected-(U1--Vin-Pad3)") (class "Default")
      (node (ref "U1") (pin "3") (pinfunction "-Vin_3") (pintype "unspecified+no_connect"))
    )
    (net (code "66") (name "unconnected-(U1-NC-Pad9)") (class "Default")
      (node (ref "U1") (pin "9") (pinfunction "NC_9") (pintype "unspecified+no_connect"))
    )
    (net (code "67") (name "unconnected-(U1-NC-Pad11)") (class "Default")
      (node (ref "U1") (pin "11") (pinfunction "NC_11") (pintype "unspecified+no_connect"))
    )
    (net (code "68") (name "unconnected-(U2-IN+-Pad1)") (class "Default")
      (node (ref "U2") (pin "1") (pinfunction "IN+_1") (pintype "unspecified"))
    )
    (net (code "69") (name "unconnected-(U2-IN--Pad2)") (class "Default")
      (node (ref "U2") (pin "2") (pinfunction "IN-_2") (pintype "unspecified"))
    )
    (net (code "70") (name "unconnected-(U2-OUT+-Pad3)") (class "Default")
      (node (ref "U2") (pin "3") (pinfunction "OUT+_3") (pintype "unspecified"))
    )
    (net (code "71") (name "unconnected-(U2-OUT--Pad4)") (class "Default")
      (node (ref "U2") (pin "4") (pinfunction "OUT-_4") (pintype "unspecified"))
    )
    (net (code "72") (name "unconnected-(U4-RX-Pad4)") (class "Default")
      (node (ref "U4") (pin "4") (pinfunction "RX_4") (pintype "unspecified"))
    )
    (net (code "73") (name "unconnected-(U4-TX-Pad3)") (class "Default")
      (node (ref "U4") (pin "3") (pinfunction "TX_3") (pintype "unspecified"))
    )
    (net (code "74") (name "unconnected-(U5-+5V-Pad2)") (class "Default")
      (node (ref "U5") (pin "2") (pinfunction "+5V_2") (pintype "unspecified"))
    )
    (net (code "75") (name "unconnected-(U5-GND-Pad1)") (class "Default")
      (node (ref "U5") (pin "1") (pinfunction "GND_1") (pintype "unspecified"))
    )
    (net (code "76") (name "unconnected-(U5-SW-Pad5)") (class "Default")
      (node (ref "U5") (pin "5") (pinfunction "SW_5") (pintype "unspecified"))
    )
    (net (code "77") (name "unconnected-(U5-VRx-Pad3)") (class "Default")
      (node (ref "U5") (pin "3") (pinfunction "VRx_3") (pintype "unspecified"))
    )
    (net (code "78") (name "unconnected-(U5-VRy-Pad4)") (class "Default")
      (node (ref "U5") (pin "4") (pinfunction "VRy_4") (pintype "unspecified"))
    )
    (net (code "79") (name "unconnected-(U6-GND-Pad8)") (class "Default")
      (node (ref "U6") (pin "8") (pinfunction "GND_8") (pintype "unspecified"))
    )
    (net (code "80") (name "unconnected-(U6-L-IN-Pad7)") (class "Default")
      (node (ref "U6") (pin "7") (pinfunction "L-IN_7") (pintype "unspecified"))
    )
    (net (code "81") (name "unconnected-(U6-R-IN-Pad9)") (class "Default")
      (node (ref "U6") (pin "9") (pinfunction "R-IN_9") (pintype "unspecified"))
    )
    (net (code "82") (name "unconnected-(U7-BT_G-Pad4)") (class "Default")
      (node (ref "U7") (pin "4") (pinfunction "BT_G_4") (pintype "unspecified"))
    )
    (net (code "83") (name "unconnected-(U7-BT_L-Pad3)") (class "Default")
      (node (ref "U7") (pin "3") (pinfunction "BT_L_3") (pintype "unspecified"))
    )
    (net (code "84") (name "unconnected-(U7-BT_R-Pad5)") (class "Default")
      (node (ref "U7") (pin "5") (pinfunction "BT_R_5") (pintype "unspecified"))
    )
    (net (code "85") (name "unconnected-(U7-GND-Pad2)") (class "Default")
      (node (ref "U7") (pin "2") (pinfunction "GND_2") (pintype "unspecified"))
    )
    (net (code "86") (name "unconnected-(U7-VCC-Pad1)") (class "Default")
      (node (ref "U7") (pin "1") (pinfunction "VCC_1") (pintype "unspecified"))
    )
    (net (code "87") (name "unconnected-(U10-+Vin-Pad22)") (class "Default")
      (node (ref "U10") (pin "22") (pinfunction "+Vin_22") (pintype "unspecified+no_connect"))
    )
    (net (code "88") (name "unconnected-(U10--Vin-Pad3)") (class "Default")
      (node (ref "U10") (pin "3") (pinfunction "-Vin_3") (pintype "unspecified+no_connect"))
    )
    (net (code "89") (name "unconnected-(U10-NC-Pad9)") (class "Default")
      (node (ref "U10") (pin "9") (pinfunction "NC_9") (pintype "unspecified+no_connect"))
    )
    (net (code "90") (name "unconnected-(U10-NC-Pad11)") (class "Default")
      (node (ref "U10") (pin "11") (pinfunction "NC_11") (pintype "unspecified+no_connect"))
    )
  )
)
